# ReturnLossFixture.net
KiCad netlist of a schematic drawn in EAGLE
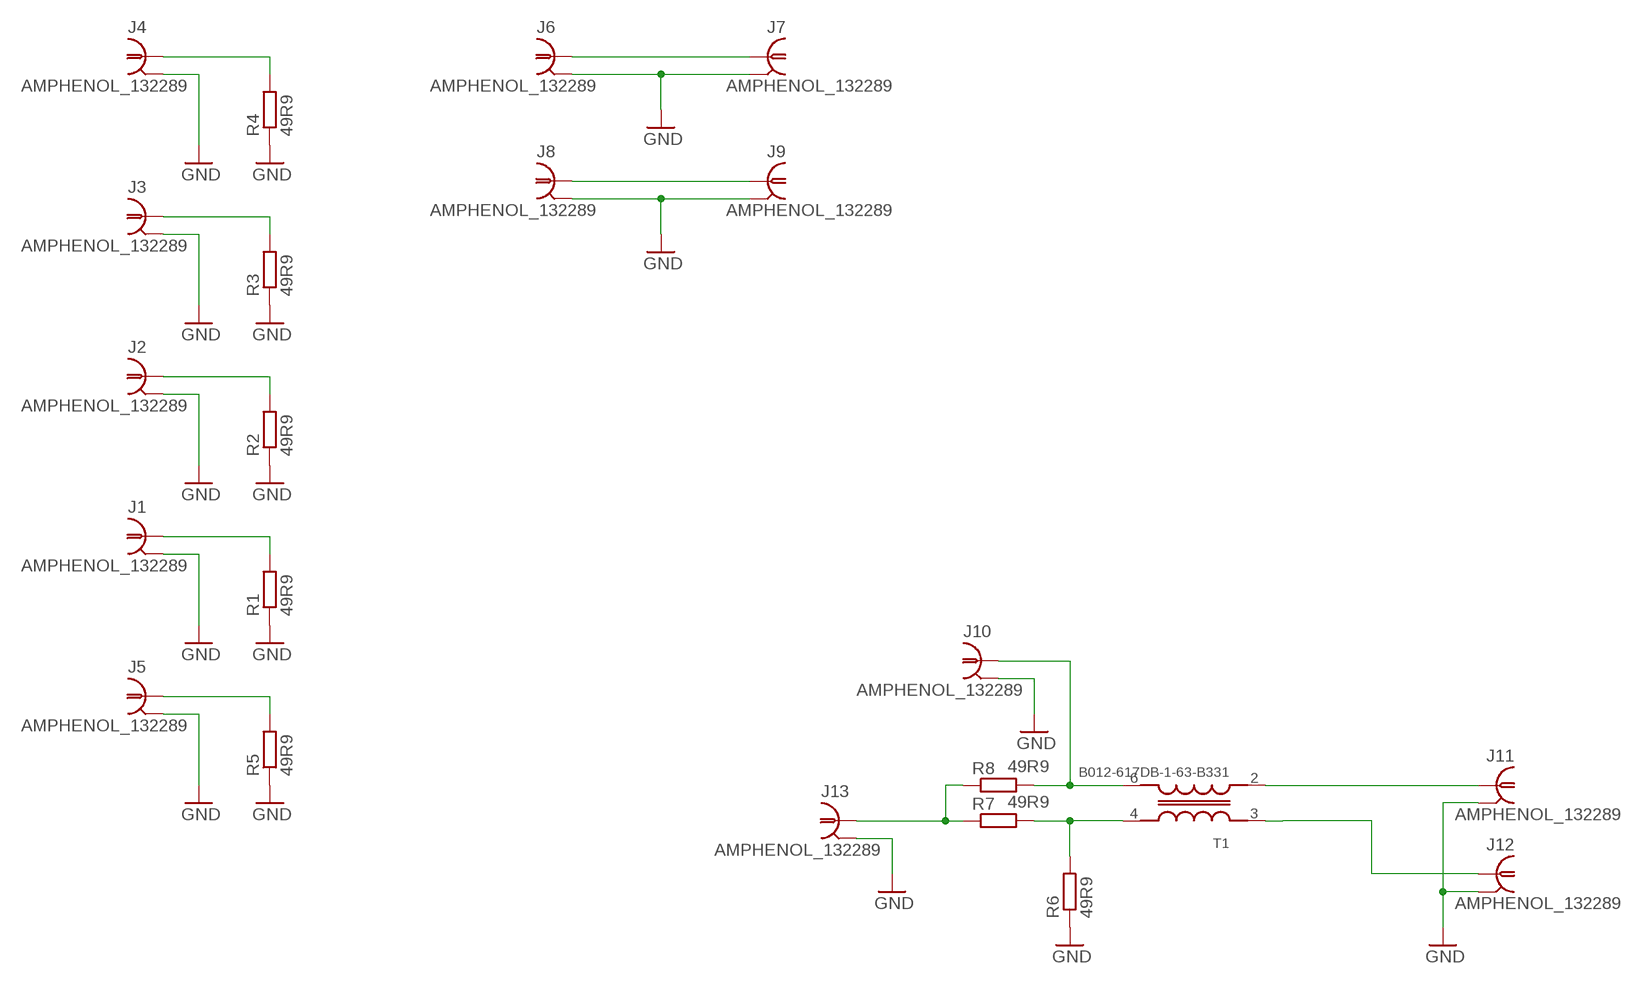
[diagram p0: schematic, sheet 1]

(export (version "E")
  (design (tool "Eeschema 10.0.6"))
  (components
    (comp (ref "J1")
      (value "AMPHENOL_132289")
      (footprint "eagle-import:AMPHENOL_132289")
      (libsource (lib "eagle-import") (part "AMPHENOL_132289"))
    )
    (comp (ref "J2")
      (value "AMPHENOL_132289")
      (footprint "eagle-import:AMPHENOL_132289")
      (libsource (lib "eagle-import") (part "AMPHENOL_132289"))
    )
    (comp (ref "J3")
      (value "AMPHENOL_132289")
      (footprint "eagle-import:AMPHENOL_132289")
      (libsource (lib "eagle-import") (part "AMPHENOL_132289"))
    )
    (comp (ref "J4")
      (value "AMPHENOL_132289")
      (footprint "eagle-import:AMPHENOL_132289")
      (libsource (lib "eagle-import") (part "AMPHENOL_132289"))
    )
    (comp (ref "J5")
      (value "AMPHENOL_132289")
      (footprint "eagle-import:AMPHENOL_132289")
      (libsource (lib "eagle-import") (part "AMPHENOL_132289"))
    )
    (comp (ref "J6")
      (value "AMPHENOL_132289")
      (footprint "eagle-import:AMPHENOL_132289")
      (libsource (lib "eagle-import") (part "AMPHENOL_132289"))
    )
    (comp (ref "J7")
      (value "AMPHENOL_132289")
      (footprint "eagle-import:AMPHENOL_132289")
      (libsource (lib "eagle-import") (part "AMPHENOL_132289"))
    )
    (comp (ref "J8")
      (value "AMPHENOL_132289")
      (footprint "eagle-import:AMPHENOL_132289")
      (libsource (lib "eagle-import") (part "AMPHENOL_132289"))
    )
    (comp (ref "J9")
      (value "AMPHENOL_132289")
      (footprint "eagle-import:AMPHENOL_132289")
      (libsource (lib "eagle-import") (part "AMPHENOL_132289"))
    )
    (comp (ref "J10")
      (value "AMPHENOL_132289")
      (footprint "eagle-import:AMPHENOL_132289")
      (libsource (lib "eagle-import") (part "AMPHENOL_132289"))
    )
    (comp (ref "J11")
      (value "AMPHENOL_132289")
      (footprint "eagle-import:AMPHENOL_132289")
      (libsource (lib "eagle-import") (part "AMPHENOL_132289"))
    )
    (comp (ref "J12")
      (value "AMPHENOL_132289")
      (footprint "eagle-import:AMPHENOL_132289")
      (libsource (lib "eagle-import") (part "AMPHENOL_132289"))
    )
    (comp (ref "J13")
      (value "AMPHENOL_132289")
      (footprint "eagle-import:AMPHENOL_132289")
      (libsource (lib "eagle-import") (part "AMPHENOL_132289"))
    )
    (comp (ref "R1")
      (value "49R9")
      (footprint "eagle-import:R0402")
      (libsource (lib "eagle-import") (part "R-EU_R0402"))
    )
    (comp (ref "R2")
      (value "49R9")
      (footprint "eagle-import:R0402")
      (libsource (lib "eagle-import") (part "R-EU_R0402"))
    )
    (comp (ref "R3")
      (value "49R9")
      (footprint "eagle-import:R0402")
      (libsource (lib "eagle-import") (part "R-EU_R0402"))
    )
    (comp (ref "R4")
      (value "49R9")
      (footprint "eagle-import:R0402")
      (libsource (lib "eagle-import") (part "R-EU_R0402"))
    )
    (comp (ref "R5")
      (value "49R9")
      (footprint "eagle-import:R0402")
      (libsource (lib "eagle-import") (part "R-EU_R0402"))
    )
    (comp (ref "R6")
      (value "49R9")
      (footprint "eagle-import:R0402")
      (libsource (lib "eagle-import") (part "R-EU_R0402"))
    )
    (comp (ref "R7")
      (value "49R9")
      (footprint "eagle-import:R0402")
      (libsource (lib "eagle-import") (part "R-EU_R0402"))
    )
    (comp (ref "R8")
      (value "49R9")
      (footprint "eagle-import:R0402")
      (libsource (lib "eagle-import") (part "R-EU_R0402"))
    )
    (comp (ref "T1")
      (value "B012-617DB-1-63-B331")
      (footprint "eagle-import:EASTEVER_BALUN")
      (libsource (lib "eagle-import") (part "B012-617DB-1-63-B331"))
    )
  )
  (nets
    (net (code "1") (name "GND") (class "Default")
      (node (ref "J1") (pin "G@1") (pinfunction "2_G@1") (pintype "passive"))
      (node (ref "J1") (pin "G@2") (pinfunction "2_G@2") (pintype "passive"))
      (node (ref "J1") (pin "G@3") (pinfunction "2_G@3") (pintype "passive"))
      (node (ref "J1") (pin "G@4") (pinfunction "2_G@4") (pintype "passive"))
      (node (ref "J10") (pin "G@1") (pinfunction "2_G@1") (pintype "passive"))
      (node (ref "J10") (pin "G@2") (pinfunction "2_G@2") (pintype "passive"))
      (node (ref "J10") (pin "G@3") (pinfunction "2_G@3") (pintype "passive"))
      (node (ref "J10") (pin "G@4") (pinfunction "2_G@4") (pintype "passive"))
      (node (ref "J11") (pin "G@1") (pinfunction "2_G@1") (pintype "passive"))
      (node (ref "J11") (pin "G@2") (pinfunction "2_G@2") (pintype "passive"))
      (node (ref "J11") (pin "G@3") (pinfunction "2_G@3") (pintype "passive"))
      (node (ref "J11") (pin "G@4") (pinfunction "2_G@4") (pintype "passive"))
      (node (ref "J12") (pin "G@1") (pinfunction "2_G@1") (pintype "passive"))
      (node (ref "J12") (pin "G@2") (pinfunction "2_G@2") (pintype "passive"))
      (node (ref "J12") (pin "G@3") (pinfunction "2_G@3") (pintype "passive"))
      (node (ref "J12") (pin "G@4") (pinfunction "2_G@4") (pintype "passive"))
      (node (ref "J13") (pin "G@1") (pinfunction "2_G@1") (pintype "passive"))
      (node (ref "J13") (pin "G@2") (pinfunction "2_G@2") (pintype "passive"))
      (node (ref "J13") (pin "G@3") (pinfunction "2_G@3") (pintype "passive"))
      (node (ref "J13") (pin "G@4") (pinfunction "2_G@4") (pintype "passive"))
      (node (ref "J2") (pin "G@1") (pinfunction "2_G@1") (pintype "passive"))
      (node (ref "J2") (pin "G@2") (pinfunction "2_G@2") (pintype "passive"))
      (node (ref "J2") (pin "G@3") (pinfunction "2_G@3") (pintype "passive"))
      (node (ref "J2") (pin "G@4") (pinfunction "2_G@4") (pintype "passive"))
      (node (ref "J3") (pin "G@1") (pinfunction "2_G@1") (pintype "passive"))
      (node (ref "J3") (pin "G@2") (pinfunction "2_G@2") (pintype "passive"))
      (node (ref "J3") (pin "G@3") (pinfunction "2_G@3") (pintype "passive"))
      (node (ref "J3") (pin "G@4") (pinfunction "2_G@4") (pintype "passive"))
      (node (ref "J4") (pin "G@1") (pinfunction "2_G@1") (pintype "passive"))
      (node (ref "J4") (pin "G@2") (pinfunction "2_G@2") (pintype "passive"))
      (node (ref "J4") (pin "G@3") (pinfunction "2_G@3") (pintype "passive"))
      (node (ref "J4") (pin "G@4") (pinfunction "2_G@4") (pintype "passive"))
      (node (ref "J5") (pin "G@1") (pinfunction "2_G@1") (pintype "passive"))
      (node (ref "J5") (pin "G@2") (pinfunction "2_G@2") (pintype "passive"))
      (node (ref "J5") (pin "G@3") (pinfunction "2_G@3") (pintype "passive"))
      (node (ref "J5") (pin "G@4") (pinfunction "2_G@4") (pintype "passive"))
      (node (ref "J6") (pin "G@1") (pinfunction "2_G@1") (pintype "passive"))
      (node (ref "J6") (pin "G@2") (pinfunction "2_G@2") (pintype "passive"))
      (node (ref "J6") (pin "G@3") (pinfunction "2_G@3") (pintype "passive"))
      (node (ref "J6") (pin "G@4") (pinfunction "2_G@4") (pintype "passive"))
      (node (ref "J7") (pin "G@1") (pinfunction "2_G@1") (pintype "passive"))
      (node (ref "J7") (pin "G@2") (pinfunction "2_G@2") (pintype "passive"))
      (node (ref "J7") (pin "G@3") (pinfunction "2_G@3") (pintype "passive"))
      (node (ref "J7") (pin "G@4") (pinfunction "2_G@4") (pintype "passive"))
      (node (ref "J8") (pin "G@1") (pinfunction "2_G@1") (pintype "passive"))
      (node (ref "J8") (pin "G@2") (pinfunction "2_G@2") (pintype "passive"))
      (node (ref "J8") (pin "G@3") (pinfunction "2_G@3") (pintype "passive"))
      (node (ref "J8") (pin "G@4") (pinfunction "2_G@4") (pintype "passive"))
      (node (ref "J9") (pin "G@1") (pinfunction "2_G@1") (pintype "passive"))
      (node (ref "J9") (pin "G@2") (pinfunction "2_G@2") (pintype "passive"))
      (node (ref "J9") (pin "G@3") (pinfunction "2_G@3") (pintype "passive"))
      (node (ref "J9") (pin "G@4") (pinfunction "2_G@4") (pintype "passive"))
      (node (ref "R1") (pin "1") (pinfunction "1_1") (pintype "passive"))
      (node (ref "R2") (pin "1") (pinfunction "1_1") (pintype "passive"))
      (node (ref "R3") (pin "1") (pinfunction "1_1") (pintype "passive"))
      (node (ref "R4") (pin "1") (pinfunction "1_1") (pintype "passive"))
      (node (ref "R5") (pin "1") (pinfunction "1_1") (pintype "passive"))
      (node (ref "R6") (pin "1") (pinfunction "1_1") (pintype "passive"))
    )
    (net (code "2") (name "Net-(J1-Pad1)") (class "Default")
      (node (ref "J1") (pin "1") (pinfunction "1_1") (pintype "passive"))
      (node (ref "R1") (pin "2") (pinfunction "2_2") (pintype "passive"))
    )
    (net (code "3") (name "Net-(J2-Pad1)") (class "Default")
      (node (ref "J2") (pin "1") (pinfunction "1_1") (pintype "passive"))
      (node (ref "R2") (pin "2") (pinfunction "2_2") (pintype "passive"))
    )
    (net (code "4") (name "Net-(J3-Pad1)") (class "Default")
      (node (ref "J3") (pin "1") (pinfunction "1_1") (pintype "passive"))
      (node (ref "R3") (pin "2") (pinfunction "2_2") (pintype "passive"))
    )
    (net (code "5") (name "Net-(J4-Pad1)") (class "Default")
      (node (ref "J4") (pin "1") (pinfunction "1_1") (pintype "passive"))
      (node (ref "R4") (pin "2") (pinfunction "2_2") (pintype "passive"))
    )
    (net (code "6") (name "Net-(J5-Pad1)") (class "Default")
      (node (ref "J5") (pin "1") (pinfunction "1_1") (pintype "passive"))
      (node (ref "R5") (pin "2") (pinfunction "2_2") (pintype "passive"))
    )
    (net (code "7") (name "Net-(J6-Pad1)") (class "Default")
      (node (ref "J6") (pin "1") (pinfunction "1_1") (pintype "passive"))
      (node (ref "J7") (pin "1") (pinfunction "1_1") (pintype "passive"))
    )
    (net (code "8") (name "Net-(J8-Pad1)") (class "Default")
      (node (ref "J8") (pin "1") (pinfunction "1_1") (pintype "passive"))
      (node (ref "J9") (pin "1") (pinfunction "1_1") (pintype "passive"))
    )
    (net (code "9") (name "Net-(J13-Pad1)") (class "Default")
      (node (ref "J13") (pin "1") (pinfunction "1_1") (pintype "passive"))
      (node (ref "R7") (pin "1") (pinfunction "1_1") (pintype "passive"))
      (node (ref "R8") (pin "1") (pinfunction "1_1") (pintype "passive"))
    )
    (net (code "10") (name "Net-(T1-IN+)") (class "Default")
      (node (ref "J12") (pin "1") (pinfunction "1_1") (pintype "passive"))
      (node (ref "T1") (pin "3") (pinfunction "IN+_3") (pintype "bidirectional"))
    )
    (net (code "11") (name "Net-(T1-IN-)") (class "Default")
      (node (ref "J11") (pin "1") (pinfunction "1_1") (pintype "passive"))
      (node (ref "T1") (pin "2") (pinfunction "IN-_2") (pintype "bidirectional"))
    )
    (net (code "12") (name "Net-(T1-OUT+)") (class "Default")
      (node (ref "R6") (pin "2") (pinfunction "2_2") (pintype "passive"))
      (node (ref "R7") (pin "2") (pinfunction "2_2") (pintype "passive"))
      (node (ref "T1") (pin "4") (pinfunction "OUT+_4") (pintype "bidirectional"))
    )
    (net (code "13") (name "Net-(T1-OUT-)") (class "Default")
      (node (ref "J10") (pin "1") (pinfunction "1_1") (pintype "passive"))
      (node (ref "R8") (pin "2") (pinfunction "2_2") (pintype "passive"))
      (node (ref "T1") (pin "6") (pinfunction "OUT-_6") (pintype "bidirectional"))
    )
  )
)
